# OpenTx-SPort-Bridge_v040.net
KiCad netlist of a schematic drawn in EAGLE
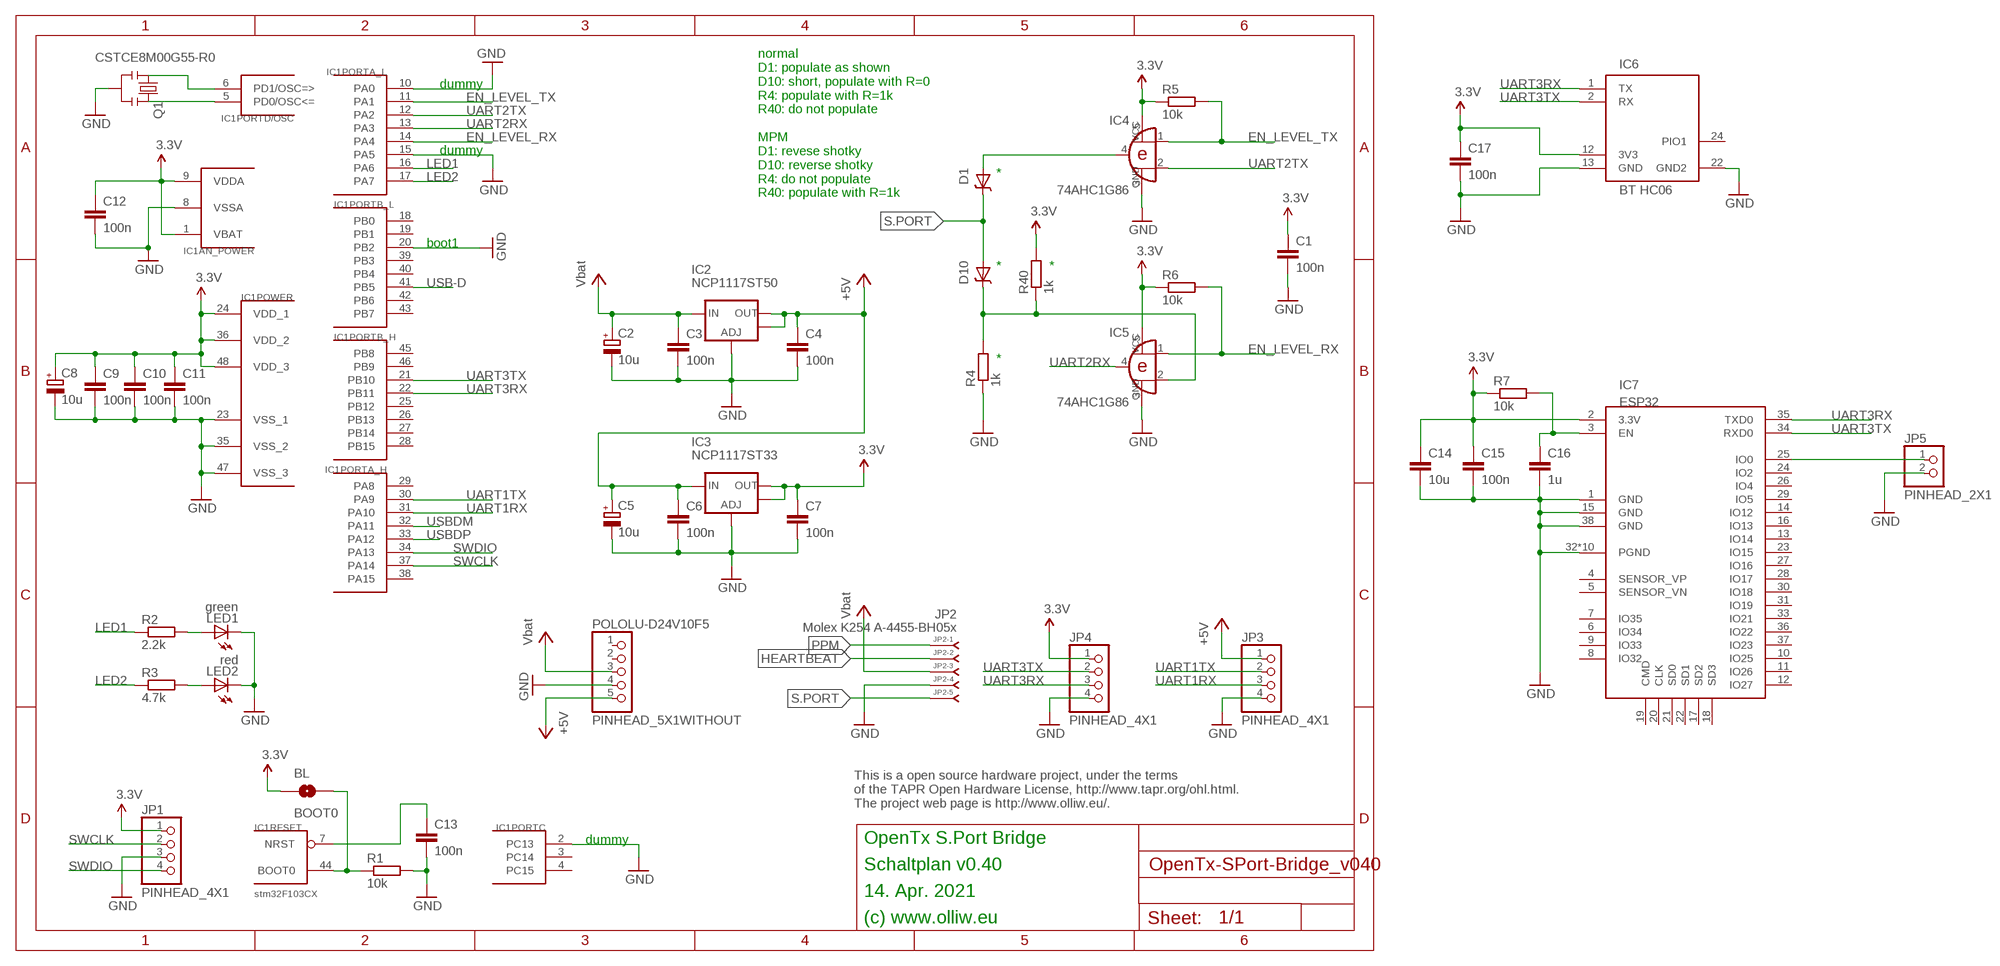
[diagram p0: schematic, sheet 1]

(export (version "E")
  (design (tool "Eeschema 10.0.6"))
  (components
    (comp (ref "BL")
      (value "BOOT0")
      (footprint "eagle-import:SJ_2S-NO")
      (libsource (lib "eagle-import") (part "SOLDERJUMPERNO"))
    )
    (comp (ref "C1")
      (value "100n")
      (footprint "eagle-import:C0603")
      (libsource (lib "eagle-import") (part "C-EUC0603"))
    )
    (comp (ref "C2")
      (value "10u")
      (footprint "eagle-import:SMC_A")
      (libsource (lib "eagle-import") (part "CPOL-EUSMCA"))
    )
    (comp (ref "C3")
      (value "100n")
      (footprint "eagle-import:C0603")
      (libsource (lib "eagle-import") (part "C-EUC0603"))
    )
    (comp (ref "C4")
      (value "100n")
      (footprint "eagle-import:C0603")
      (libsource (lib "eagle-import") (part "C-EUC0603"))
    )
    (comp (ref "C5")
      (value "10u")
      (footprint "eagle-import:SMC_A")
      (libsource (lib "eagle-import") (part "CPOL-EUSMCA"))
    )
    (comp (ref "C6")
      (value "100n")
      (footprint "eagle-import:C0603")
      (libsource (lib "eagle-import") (part "C-EUC0603"))
    )
    (comp (ref "C7")
      (value "100n")
      (footprint "eagle-import:C0603")
      (libsource (lib "eagle-import") (part "C-EUC0603"))
    )
    (comp (ref "C8")
      (value "10u")
      (footprint "eagle-import:SMC_A")
      (libsource (lib "eagle-import") (part "CPOL-EUSMCA"))
    )
    (comp (ref "C9")
      (value "100n")
      (footprint "eagle-import:C0603")
      (libsource (lib "eagle-import") (part "C-EUC0603"))
    )
    (comp (ref "C10")
      (value "100n")
      (footprint "eagle-import:C0603")
      (libsource (lib "eagle-import") (part "C-EUC0603"))
    )
    (comp (ref "C11")
      (value "100n")
      (footprint "eagle-import:C0603")
      (libsource (lib "eagle-import") (part "C-EUC0603"))
    )
    (comp (ref "C12")
      (value "100n")
      (footprint "eagle-import:C0603")
      (libsource (lib "eagle-import") (part "C-EUC0603"))
    )
    (comp (ref "C13")
      (value "100n")
      (footprint "eagle-import:C0603")
      (libsource (lib "eagle-import") (part "C-EUC0603"))
    )
    (comp (ref "C14")
      (value "10u")
      (footprint "eagle-import:C0805")
      (libsource (lib "eagle-import") (part "C-EUC0805"))
    )
    (comp (ref "C15")
      (value "100n")
      (footprint "eagle-import:C0603")
      (libsource (lib "eagle-import") (part "C-EUC0603"))
    )
    (comp (ref "C16")
      (value "1u")
      (footprint "eagle-import:C0603")
      (libsource (lib "eagle-import") (part "C-EUC0603"))
    )
    (comp (ref "C17")
      (value "100n")
      (footprint "eagle-import:C0603")
      (libsource (lib "eagle-import") (part "C-EUC0603"))
    )
    (comp (ref "D1")
      (value "PMEG3010ER")
      (footprint "eagle-import:SOD123W-DIODE")
      (libsource (lib "eagle-import") (part "DIODE-SCHOTTKYSOD123-W"))
    )
    (comp (ref "D10")
      (value "PMEG3010ER")
      (footprint "eagle-import:SOD123W-DIODE")
      (libsource (lib "eagle-import") (part "DIODE-SCHOTTKYSOD123-W"))
    )
    (comp (ref "IC1")
      (value "stm32F103CX")
      (footprint "eagle-import:TQFP48")
      (libsource (lib "eagle-import") (part "STM32F10XCXT6"))
    )
    (comp (ref "IC2")
      (value "NCP1117ST50")
      (footprint "eagle-import:SOT223")
      (libsource (lib "eagle-import") (part "V_REG_LM1117SOT223"))
    )
    (comp (ref "IC3")
      (value "NCP1117ST33")
      (footprint "eagle-import:SOT223")
      (libsource (lib "eagle-import") (part "V_REG_LM1117SOT223"))
    )
    (comp (ref "IC4")
      (value "74AHC1G86")
      (footprint "eagle-import:SOT23-5-VER1")
      (libsource (lib "eagle-import") (part "74AHC1G86"))
    )
    (comp (ref "IC5")
      (value "74AHC1G86")
      (footprint "eagle-import:SOT23-5-VER1")
      (libsource (lib "eagle-import") (part "74AHC1G86"))
    )
    (comp (ref "IC6")
      (value "BT HC06")
      (footprint "eagle-import:BT_HC05_BASIC")
      (libsource (lib "eagle-import") (part "HC06-BASIC"))
    )
    (comp (ref "IC7")
      (value "ESP32")
      (footprint "eagle-import:ESP-WROOM-32D")
      (libsource (lib "eagle-import") (part "ESP32"))
    )
    (comp (ref "JP1")
      (value "PINHEAD_4X1")
      (footprint "eagle-import:PINHEAD_4X1")
      (libsource (lib "eagle-import") (part "PINHEAD_4X1"))
    )
    (comp (ref "JP2")
      (value "Molex K254 A-4455-BH05x")
      (footprint "eagle-import:4455-B05")
      (libsource (lib "eagle-import") (part "4455-B05_S"))
    )
    (comp (ref "JP3")
      (value "PINHEAD_4X1")
      (footprint "eagle-import:PINHEAD_4X1")
      (libsource (lib "eagle-import") (part "PINHEAD_4X1"))
    )
    (comp (ref "JP4")
      (value "PINHEAD_4X1")
      (footprint "eagle-import:PINHEAD_4X1")
      (libsource (lib "eagle-import") (part "PINHEAD_4X1"))
    )
    (comp (ref "JP5")
      (value "PINHEAD_2X1")
      (footprint "eagle-import:PINHEAD_2X1")
      (libsource (lib "eagle-import") (part "PINHEAD_2X1"))
    )
    (comp (ref "LED1")
      (value "green")
      (footprint "eagle-import:LED3MM")
      (libsource (lib "eagle-import") (part "LED3MM"))
    )
    (comp (ref "LED2")
      (value "red")
      (footprint "eagle-import:LED3MM")
      (libsource (lib "eagle-import") (part "LED3MM"))
    )
    (comp (ref "POLOLU-D24V10F5")
      (value "PINHEAD_5X1WITHOUT")
      (footprint "eagle-import:PINHEAD_5X1_WO")
      (libsource (lib "eagle-import") (part "PINHEAD_5X1WITHOUT"))
    )
    (comp (ref "Q1")
      (value "CSTCE8M00G55-R0")
      (footprint "eagle-import:RESONATOR-SMD")
      (libsource (lib "eagle-import") (part "RESONATORSMD"))
    )
    (comp (ref "R1")
      (value "10k")
      (footprint "eagle-import:R0603")
      (libsource (lib "eagle-import") (part "R-EU_R0603"))
    )
    (comp (ref "R2")
      (value "2.2k")
      (footprint "eagle-import:R0603")
      (libsource (lib "eagle-import") (part "R-EU_R0603"))
    )
    (comp (ref "R3")
      (value "4.7k")
      (footprint "eagle-import:R0603")
      (libsource (lib "eagle-import") (part "R-EU_R0603"))
    )
    (comp (ref "R4")
      (value "1k")
      (footprint "eagle-import:R0603")
      (libsource (lib "eagle-import") (part "R-EU_R0603"))
    )
    (comp (ref "R5")
      (value "10k")
      (footprint "eagle-import:R0603")
      (libsource (lib "eagle-import") (part "R-EU_R0603"))
    )
    (comp (ref "R6")
      (value "10k")
      (footprint "eagle-import:R0603")
      (libsource (lib "eagle-import") (part "R-EU_R0603"))
    )
    (comp (ref "R7")
      (value "10k")
      (footprint "eagle-import:R0603")
      (libsource (lib "eagle-import") (part "R-EU_R0603"))
    )
    (comp (ref "R40")
      (value "1k")
      (footprint "eagle-import:R0603")
      (libsource (lib "eagle-import") (part "R-EU_R0603"))
    )
  )
  (nets
    (net (code "1") (name "+5V") (class "Default")
      (node (ref "C4") (pin "1") (pinfunction "1_1") (pintype "passive"))
      (node (ref "C5") (pin "+") (pinfunction "+_+") (pintype "passive"))
      (node (ref "C6") (pin "1") (pinfunction "1_1") (pintype "passive"))
      (node (ref "IC2") (pin "2") (pinfunction "OUT_2") (pintype "output"))
      (node (ref "IC2") (pin "4") (pinfunction "OUT_4") (pintype "output"))
      (node (ref "IC3") (pin "3") (pinfunction "IN_3") (pintype "input"))
      (node (ref "JP3") (pin "1") (pinfunction "1_1") (pintype "passive"))
      (node (ref "POLOLU-D24V10F5") (pin "5") (pinfunction "5_5") (pintype "passive"))
    )
    (net (code "2") (name "/EN_LEVEL_RX") (class "Default")
      (node (ref "IC1") (pin "14") (pinfunction "PA4_14") (pintype "bidirectional"))
      (node (ref "IC5") (pin "1") (pinfunction "I0_1") (pintype "input"))
      (node (ref "R6") (pin "2") (pinfunction "2_2") (pintype "passive"))
    )
    (net (code "3") (name "/EN_LEVEL_TX") (class "Default")
      (node (ref "IC1") (pin "11") (pinfunction "PA1_11") (pintype "bidirectional"))
      (node (ref "IC4") (pin "1") (pinfunction "I0_1") (pintype "input"))
      (node (ref "R5") (pin "2") (pinfunction "2_2") (pintype "passive"))
    )
    (net (code "4") (name "/LED1") (class "Default")
      (node (ref "IC1") (pin "16") (pinfunction "PA6_16") (pintype "bidirectional"))
      (node (ref "R2") (pin "1") (pinfunction "1_1") (pintype "passive"))
    )
    (net (code "5") (name "/LED2") (class "Default")
      (node (ref "IC1") (pin "17") (pinfunction "PA7_17") (pintype "bidirectional"))
      (node (ref "R3") (pin "1") (pinfunction "1_1") (pintype "passive"))
    )
    (net (code "6") (name "/SWCLK") (class "Default")
      (node (ref "IC1") (pin "37") (pinfunction "PA14_37") (pintype "bidirectional"))
      (node (ref "JP1") (pin "2") (pinfunction "2_2") (pintype "passive"))
    )
    (net (code "7") (name "/SWDIO") (class "Default")
      (node (ref "IC1") (pin "34") (pinfunction "PA13_34") (pintype "bidirectional"))
      (node (ref "JP1") (pin "4") (pinfunction "4_4") (pintype "passive"))
    )
    (net (code "8") (name "/UART1RX") (class "Default")
      (node (ref "IC1") (pin "31") (pinfunction "PA10_31") (pintype "bidirectional"))
      (node (ref "JP3") (pin "3") (pinfunction "3_3") (pintype "passive"))
    )
    (net (code "9") (name "/UART1TX") (class "Default")
      (node (ref "IC1") (pin "30") (pinfunction "PA9_30") (pintype "bidirectional"))
      (node (ref "JP3") (pin "2") (pinfunction "2_2") (pintype "passive"))
    )
    (net (code "10") (name "/UART2RX") (class "Default")
      (node (ref "IC1") (pin "13") (pinfunction "PA3_13") (pintype "bidirectional"))
      (node (ref "IC5") (pin "4") (pinfunction "O_4") (pintype "output"))
    )
    (net (code "11") (name "/UART2TX") (class "Default")
      (node (ref "IC1") (pin "12") (pinfunction "PA2_12") (pintype "bidirectional"))
      (node (ref "IC4") (pin "2") (pinfunction "I1_2") (pintype "input"))
    )
    (net (code "12") (name "/UART3RX") (class "Default")
      (node (ref "IC1") (pin "22") (pinfunction "PB11_22") (pintype "bidirectional"))
      (node (ref "IC6") (pin "1") (pinfunction "TX_1") (pintype "bidirectional"))
      (node (ref "IC7") (pin "35") (pinfunction "TXD0_35") (pintype "bidirectional"))
      (node (ref "JP4") (pin "3") (pinfunction "3_3") (pintype "passive"))
    )
    (net (code "13") (name "/UART3TX") (class "Default")
      (node (ref "IC1") (pin "21") (pinfunction "PB10_21") (pintype "bidirectional"))
      (node (ref "IC6") (pin "2") (pinfunction "RX_2") (pintype "bidirectional"))
      (node (ref "IC7") (pin "34") (pinfunction "RXD0_34") (pintype "bidirectional"))
      (node (ref "JP4") (pin "2") (pinfunction "2_2") (pintype "passive"))
    )
    (net (code "14") (name "/USB-D") (class "Default")
      (node (ref "IC1") (pin "41") (pinfunction "PB5_41") (pintype "bidirectional"))
    )
    (net (code "15") (name "/USBDM") (class "Default")
      (node (ref "IC1") (pin "32") (pinfunction "PA11_32") (pintype "bidirectional"))
    )
    (net (code "16") (name "/USBDP") (class "Default")
      (node (ref "IC1") (pin "33") (pinfunction "PA12_33") (pintype "bidirectional"))
    )
    (net (code "17") (name "3.3V") (class "Default")
      (node (ref "BL") (pin "1") (pinfunction "1_1") (pintype "passive"))
      (node (ref "C1") (pin "1") (pinfunction "1_1") (pintype "passive"))
      (node (ref "C10") (pin "1") (pinfunction "1_1") (pintype "passive"))
      (node (ref "C11") (pin "1") (pinfunction "1_1") (pintype "passive"))
      (node (ref "C12") (pin "1") (pinfunction "1_1") (pintype "passive"))
      (node (ref "C14") (pin "1") (pinfunction "1_1") (pintype "passive"))
      (node (ref "C15") (pin "1") (pinfunction "1_1") (pintype "passive"))
      (node (ref "C17") (pin "1") (pinfunction "1_1") (pintype "passive"))
      (node (ref "C7") (pin "1") (pinfunction "1_1") (pintype "passive"))
      (node (ref "C8") (pin "+") (pinfunction "+_+") (pintype "passive"))
      (node (ref "C9") (pin "1") (pinfunction "1_1") (pintype "passive"))
      (node (ref "IC1") (pin "1") (pinfunction "VBAT_1") (pintype "power_in"))
      (node (ref "IC1") (pin "24") (pinfunction "VDD_1_24") (pintype "power_in"))
      (node (ref "IC1") (pin "36") (pinfunction "VDD_2_36") (pintype "power_in"))
      (node (ref "IC1") (pin "48") (pinfunction "VDD_3_48") (pintype "power_in"))
      (node (ref "IC1") (pin "9") (pinfunction "VDDA_9") (pintype "power_in"))
      (node (ref "IC3") (pin "2") (pinfunction "OUT_2") (pintype "output"))
      (node (ref "IC3") (pin "4") (pinfunction "OUT_4") (pintype "output"))
      (node (ref "IC4") (pin "5") (pinfunction "VCC_5") (pintype "power_in"))
      (node (ref "IC5") (pin "5") (pinfunction "VCC_5") (pintype "power_in"))
      (node (ref "IC6") (pin "12") (pinfunction "3V3_12") (pintype "bidirectional"))
      (node (ref "IC7") (pin "2") (pinfunction "3.3V_2") (pintype "power_in"))
      (node (ref "JP1") (pin "1") (pinfunction "1_1") (pintype "passive"))
      (node (ref "JP4") (pin "1") (pinfunction "1_1") (pintype "passive"))
      (node (ref "R40") (pin "2") (pinfunction "2_2") (pintype "passive"))
      (node (ref "R5") (pin "1") (pinfunction "1_1") (pintype "passive"))
      (node (ref "R6") (pin "1") (pinfunction "1_1") (pintype "passive"))
      (node (ref "R7") (pin "1") (pinfunction "1_1") (pintype "passive"))
    )
    (net (code "18") (name "GND") (class "Default")
      (node (ref "C1") (pin "2") (pinfunction "2_2") (pintype "passive"))
      (node (ref "C10") (pin "2") (pinfunction "2_2") (pintype "passive"))
      (node (ref "C11") (pin "2") (pinfunction "2_2") (pintype "passive"))
      (node (ref "C12") (pin "2") (pinfunction "2_2") (pintype "passive"))
      (node (ref "C13") (pin "2") (pinfunction "2_2") (pintype "passive"))
      (node (ref "C14") (pin "2") (pinfunction "2_2") (pintype "passive"))
      (node (ref "C15") (pin "2") (pinfunction "2_2") (pintype "passive"))
      (node (ref "C16") (pin "2") (pinfunction "2_2") (pintype "passive"))
      (node (ref "C17") (pin "2") (pinfunction "2_2") (pintype "passive"))
      (node (ref "C2") (pin "-") (pinfunction "-_-") (pintype "passive"))
      (node (ref "C3") (pin "2") (pinfunction "2_2") (pintype "passive"))
      (node (ref "C4") (pin "2") (pinfunction "2_2") (pintype "passive"))
      (node (ref "C5") (pin "-") (pinfunction "-_-") (pintype "passive"))
      (node (ref "C6") (pin "2") (pinfunction "2_2") (pintype "passive"))
      (node (ref "C7") (pin "2") (pinfunction "2_2") (pintype "passive"))
      (node (ref "C8") (pin "-") (pinfunction "-_-") (pintype "passive"))
      (node (ref "C9") (pin "2") (pinfunction "2_2") (pintype "passive"))
      (node (ref "IC1") (pin "10") (pinfunction "PA0_10") (pintype "bidirectional"))
      (node (ref "IC1") (pin "15") (pinfunction "PA5_15") (pintype "bidirectional"))
      (node (ref "IC1") (pin "2") (pinfunction "PC13_2") (pintype "bidirectional"))
      (node (ref "IC1") (pin "20") (pinfunction "PB2_20") (pintype "bidirectional"))
      (node (ref "IC1") (pin "23") (pinfunction "VSS_1_23") (pintype "power_in"))
      (node (ref "IC1") (pin "35") (pinfunction "VSS_2_35") (pintype "power_in"))
      (node (ref "IC1") (pin "47") (pinfunction "VSS_3_47") (pintype "power_in"))
      (node (ref "IC1") (pin "8") (pinfunction "VSSA_8") (pintype "power_in"))
      (node (ref "IC2") (pin "1") (pinfunction "ADJ_1") (pintype "input"))
      (node (ref "IC3") (pin "1") (pinfunction "ADJ_1") (pintype "input"))
      (node (ref "IC4") (pin "3") (pinfunction "GND_3") (pintype "power_in"))
      (node (ref "IC5") (pin "3") (pinfunction "GND_3") (pintype "power_in"))
      (node (ref "IC6") (pin "13") (pinfunction "GND_13") (pintype "bidirectional"))
      (node (ref "IC6") (pin "22") (pinfunction "GND2_22") (pintype "bidirectional"))
      (node (ref "IC7") (pin "1") (pinfunction "GND_1") (pintype "power_in"))
      (node (ref "IC7") (pin "15") (pinfunction "GND_15") (pintype "power_in"))
      (node (ref "IC7") (pin "32") (pinfunction "PGND_32") (pintype "power_in"))
      (node (ref "IC7") (pin "38") (pinfunction "GND_38") (pintype "power_in"))
      (node (ref "IC7") (pin "39") (pinfunction "PGND_39") (pintype "power_in"))
      (node (ref "IC7") (pin "40") (pinfunction "PGND_40") (pintype "power_in"))
      (node (ref "IC7") (pin "41") (pinfunction "PGND_41") (pintype "power_in"))
      (node (ref "IC7") (pin "42") (pinfunction "PGND_42") (pintype "power_in"))
      (node (ref "IC7") (pin "43") (pinfunction "PGND_43") (pintype "power_in"))
      (node (ref "IC7") (pin "44") (pinfunction "PGND_44") (pintype "power_in"))
      (node (ref "IC7") (pin "45") (pinfunction "PGND_45") (pintype "power_in"))
      (node (ref "IC7") (pin "46") (pinfunction "PGND_46") (pintype "power_in"))
      (node (ref "IC7") (pin "47") (pinfunction "PGND_47") (pintype "power_in"))
      (node (ref "JP1") (pin "3") (pinfunction "3_3") (pintype "passive"))
      (node (ref "JP2") (pin "4") (pinfunction "J_4") (pintype "passive"))
      (node (ref "JP3") (pin "4") (pinfunction "4_4") (pintype "passive"))
      (node (ref "JP4") (pin "4") (pinfunction "4_4") (pintype "passive"))
      (node (ref "JP5") (pin "2") (pinfunction "2_2") (pintype "passive"))
      (node (ref "LED1") (pin "K") (pinfunction "C_K") (pintype "passive"))
      (node (ref "LED2") (pin "K") (pinfunction "C_K") (pintype "passive"))
      (node (ref "POLOLU-D24V10F5") (pin "4") (pinfunction "4_4") (pintype "passive"))
      (node (ref "Q1") (pin "2") (pinfunction "2_2") (pintype "passive"))
      (node (ref "R1") (pin "2") (pinfunction "2_2") (pintype "passive"))
      (node (ref "R4") (pin "1") (pinfunction "1_1") (pintype "passive"))
    )
    (net (code "19") (name "HEARTBEAT") (class "Default")
      (node (ref "JP2") (pin "2") (pinfunction "J_2") (pintype "passive"))
    )
    (net (code "20") (name "Net-(IC1G-PD0{slash}OSC<=)") (class "Default")
      (node (ref "IC1") (pin "5") (pinfunction "PD0/OSC<=_5") (pintype "bidirectional"))
      (node (ref "Q1") (pin "3") (pinfunction "3_3") (pintype "passive"))
    )
    (net (code "21") (name "Net-(IC1G-PD1{slash}OSC=>)") (class "Default")
      (node (ref "IC1") (pin "6") (pinfunction "PD1/OSC=>_6") (pintype "bidirectional"))
      (node (ref "Q1") (pin "1") (pinfunction "1_1") (pintype "passive"))
    )
    (net (code "22") (name "Net-(IC1I-BOOT0)") (class "Default")
      (node (ref "BL") (pin "2") (pinfunction "2_2") (pintype "passive"))
      (node (ref "IC1") (pin "44") (pinfunction "BOOT0_44") (pintype "input"))
      (node (ref "R1") (pin "1") (pinfunction "1_1") (pintype "passive"))
    )
    (net (code "23") (name "Net-(IC1I-NRST)") (class "Default")
      (node (ref "C13") (pin "1") (pinfunction "1_1") (pintype "passive"))
      (node (ref "IC1") (pin "7") (pinfunction "NRST_7") (pintype "input"))
    )
    (net (code "24") (name "Net-(IC4-O)") (class "Default")
      (node (ref "D1") (pin "A") (pinfunction "A_A") (pintype "passive"))
      (node (ref "IC4") (pin "4") (pinfunction "O_4") (pintype "output"))
    )
    (net (code "25") (name "Net-(IC5-I1)") (class "Default")
      (node (ref "D10") (pin "C") (pinfunction "C_C") (pintype "passive"))
      (node (ref "IC5") (pin "2") (pinfunction "I1_2") (pintype "input"))
      (node (ref "R4") (pin "2") (pinfunction "2_2") (pintype "passive"))
      (node (ref "R40") (pin "1") (pinfunction "1_1") (pintype "passive"))
    )
    (net (code "26") (name "Net-(IC7-EN)") (class "Default")
      (node (ref "C16") (pin "1") (pinfunction "1_1") (pintype "passive"))
      (node (ref "IC7") (pin "3") (pinfunction "EN_3") (pintype "input"))
      (node (ref "R7") (pin "2") (pinfunction "2_2") (pintype "passive"))
    )
    (net (code "27") (name "Net-(IC7-IO0)") (class "Default")
      (node (ref "IC7") (pin "25") (pinfunction "IO0_25") (pintype "bidirectional"))
      (node (ref "JP5") (pin "1") (pinfunction "1_1") (pintype "passive"))
    )
    (net (code "28") (name "Net-(LED1-PadA)") (class "Default")
      (node (ref "LED1") (pin "A") (pinfunction "A_A") (pintype "passive"))
      (node (ref "R2") (pin "2") (pinfunction "2_2") (pintype "passive"))
    )
    (net (code "29") (name "Net-(LED2-PadA)") (class "Default")
      (node (ref "LED2") (pin "A") (pinfunction "A_A") (pintype "passive"))
      (node (ref "R3") (pin "2") (pinfunction "2_2") (pintype "passive"))
    )
    (net (code "30") (name "PPM") (class "Default")
      (node (ref "JP2") (pin "1") (pinfunction "J_1") (pintype "passive"))
    )
    (net (code "31") (name "S.PORT") (class "Default")
      (node (ref "D1") (pin "C") (pinfunction "C_C") (pintype "passive"))
      (node (ref "D10") (pin "A") (pinfunction "A_A") (pintype "passive"))
      (node (ref "JP2") (pin "5") (pinfunction "J_5") (pintype "passive"))
    )
    (net (code "32") (name "Vbat") (class "Default")
      (node (ref "C2") (pin "+") (pinfunction "+_+") (pintype "passive"))
      (node (ref "C3") (pin "1") (pinfunction "1_1") (pintype "passive"))
      (node (ref "IC2") (pin "3") (pinfunction "IN_3") (pintype "input"))
      (node (ref "JP2") (pin "3") (pinfunction "J_3") (pintype "passive"))
      (node (ref "POLOLU-D24V10F5") (pin "3") (pinfunction "3_3") (pintype "passive"))
    )
    (net (code "33") (name "unconnected-(IC1B-PA8-Pad29)") (class "Default")
      (node (ref "IC1") (pin "29") (pinfunction "PA8_29") (pintype "bidirectional"))
    )
    (net (code "34") (name "unconnected-(IC1B-PA15-Pad38)") (class "Default")
      (node (ref "IC1") (pin "38") (pinfunction "PA15_38") (pintype "bidirectional"))
    )
    (net (code "35") (name "unconnected-(IC1D-PB8-Pad45)") (class "Default")
      (node (ref "IC1") (pin "45") (pinfunction "PB8_45") (pintype "bidirectional"))
    )
    (net (code "36") (name "unconnected-(IC1D-PB9-Pad46)") (class "Default")
      (node (ref "IC1") (pin "46") (pinfunction "PB9_46") (pintype "bidirectional"))
    )
    (net (code "37") (name "unconnected-(IC1D-PB12-Pad25)") (class "Default")
      (node (ref "IC1") (pin "25") (pinfunction "PB12_25") (pintype "bidirectional"))
    )
    (net (code "38") (name "unconnected-(IC1D-PB13-Pad26)") (class "Default")
      (node (ref "IC1") (pin "26") (pinfunction "PB13_26") (pintype "bidirectional"))
    )
    (net (code "39") (name "unconnected-(IC1D-PB14-Pad27)") (class "Default")
      (node (ref "IC1") (pin "27") (pinfunction "PB14_27") (pintype "bidirectional"))
    )
    (net (code "40") (name "unconnected-(IC1D-PB15-Pad28)") (class "Default")
      (node (ref "IC1") (pin "28") (pinfunction "PB15_28") (pintype "bidirectional"))
    )
    (net (code "41") (name "unconnected-(IC1E-PB0-Pad18)") (class "Default")
      (node (ref "IC1") (pin "18") (pinfunction "PB0_18") (pintype "bidirectional"))
    )
    (net (code "42") (name "unconnected-(IC1E-PB1-Pad19)") (class "Default")
      (node (ref "IC1") (pin "19") (pinfunction "PB1_19") (pintype "bidirectional"))
    )
    (net (code "43") (name "unconnected-(IC1E-PB3-Pad39)") (class "Default")
      (node (ref "IC1") (pin "39") (pinfunction "PB3_39") (pintype "bidirectional"))
    )
    (net (code "44") (name "unconnected-(IC1E-PB4-Pad40)") (class "Default")
      (node (ref "IC1") (pin "40") (pinfunction "PB4_40") (pintype "bidirectional"))
    )
    (net (code "45") (name "unconnected-(IC1E-PB6-Pad42)") (class "Default")
      (node (ref "IC1") (pin "42") (pinfunction "PB6_42") (pintype "bidirectional"))
    )
    (net (code "46") (name "unconnected-(IC1E-PB7-Pad43)") (class "Default")
      (node (ref "IC1") (pin "43") (pinfunction "PB7_43") (pintype "bidirectional"))
    )
    (net (code "47") (name "unconnected-(IC1F-PC14-Pad3)") (class "Default")
      (node (ref "IC1") (pin "3") (pinfunction "PC14_3") (pintype "bidirectional"))
    )
    (net (code "48") (name "unconnected-(IC1F-PC15-Pad4)") (class "Default")
      (node (ref "IC1") (pin "4") (pinfunction "PC15_4") (pintype "bidirectional"))
    )
    (net (code "49") (name "unconnected-(IC6-PIO1-Pad24)") (class "Default")
      (node (ref "IC6") (pin "24") (pinfunction "PIO1_24") (pintype "bidirectional"))
    )
    (net (code "50") (name "unconnected-(IC7-CLK-Pad20)") (class "Default")
      (node (ref "IC7") (pin "20") (pinfunction "CLK_20") (pintype "bidirectional"))
    )
    (net (code "51") (name "unconnected-(IC7-CMD-Pad19)") (class "Default")
      (node (ref "IC7") (pin "19") (pinfunction "CMD_19") (pintype "bidirectional"))
    )
    (net (code "52") (name "unconnected-(IC7-IO2-Pad24)") (class "Default")
      (node (ref "IC7") (pin "24") (pinfunction "IO2_24") (pintype "bidirectional"))
    )
    (net (code "53") (name "unconnected-(IC7-IO4-Pad26)") (class "Default")
      (node (ref "IC7") (pin "26") (pinfunction "IO4_26") (pintype "bidirectional"))
    )
    (net (code "54") (name "unconnected-(IC7-IO5-Pad29)") (class "Default")
      (node (ref "IC7") (pin "29") (pinfunction "IO5_29") (pintype "bidirectional"))
    )
    (net (code "55") (name "unconnected-(IC7-IO12-Pad14)") (class "Default")
      (node (ref "IC7") (pin "14") (pinfunction "IO12_14") (pintype "bidirectional"))
    )
    (net (code "56") (name "unconnected-(IC7-IO13-Pad16)") (class "Default")
      (node (ref "IC7") (pin "16") (pinfunction "IO13_16") (pintype "bidirectional"))
    )
    (net (code "57") (name "unconnected-(IC7-IO14-Pad13)") (class "Default")
      (node (ref "IC7") (pin "13") (pinfunction "IO14_13") (pintype "bidirectional"))
    )
    (net (code "58") (name "unconnected-(IC7-IO15-Pad23)") (class "Default")
      (node (ref "IC7") (pin "23") (pinfunction "IO15_23") (pintype "bidirectional"))
    )
    (net (code "59") (name "unconnected-(IC7-IO16-Pad27)") (class "Default")
      (node (ref "IC7") (pin "27") (pinfunction "IO16_27") (pintype "bidirectional"))
    )
    (net (code "60") (name "unconnected-(IC7-IO17-Pad28)") (class "Default")
      (node (ref "IC7") (pin "28") (pinfunction "IO17_28") (pintype "bidirectional"))
    )
    (net (code "61") (name "unconnected-(IC7-IO18-Pad30)") (class "Default")
      (node (ref "IC7") (pin "30") (pinfunction "IO18_30") (pintype "bidirectional"))
    )
    (net (code "62") (name "unconnected-(IC7-IO19-Pad31)") (class "Default")
      (node (ref "IC7") (pin "31") (pinfunction "IO19_31") (pintype "bidirectional"))
    )
    (net (code "63") (name "unconnected-(IC7-IO21-Pad33)") (class "Default")
      (node (ref "IC7") (pin "33") (pinfunction "IO21_33") (pintype "bidirectional"))
    )
    (net (code "64") (name "unconnected-(IC7-IO22-Pad36)") (class "Default")
      (node (ref "IC7") (pin "36") (pinfunction "IO22_36") (pintype "bidirectional"))
    )
    (net (code "65") (name "unconnected-(IC7-IO23-Pad37)") (class "Default")
      (node (ref "IC7") (pin "37") (pinfunction "IO23_37") (pintype "bidirectional"))
    )
    (net (code "66") (name "unconnected-(IC7-IO25-Pad10)") (class "Default")
      (node (ref "IC7") (pin "10") (pinfunction "IO25_10") (pintype "bidirectional"))
    )
    (net (code "67") (name "unconnected-(IC7-IO26-Pad11)") (class "Default")
      (node (ref "IC7") (pin "11") (pinfunction "IO26_11") (pintype "bidirectional"))
    )
    (net (code "68") (name "unconnected-(IC7-IO27-Pad12)") (class "Default")
      (node (ref "IC7") (pin "12") (pinfunction "IO27_12") (pintype "bidirectional"))
    )
    (net (code "69") (name "unconnected-(IC7-IO32-Pad8)") (class "Default")
      (node (ref "IC7") (pin "8") (pinfunction "IO32_8") (pintype "bidirectional"))
    )
    (net (code "70") (name "unconnected-(IC7-IO33-Pad9)") (class "Default")
      (node (ref "IC7") (pin "9") (pinfunction "IO33_9") (pintype "bidirectional"))
    )
    (net (code "71") (name "unconnected-(IC7-IO34-Pad6)") (class "Default")
      (node (ref "IC7") (pin "6") (pinfunction "IO34_6") (pintype "bidirectional"))
    )
    (net (code "72") (name "unconnected-(IC7-IO35-Pad7)") (class "Default")
      (node (ref "IC7") (pin "7") (pinfunction "IO35_7") (pintype "bidirectional"))
    )
    (net (code "73") (name "unconnected-(IC7-SD0-Pad21)") (class "Default")
      (node (ref "IC7") (pin "21") (pinfunction "SD0_21") (pintype "bidirectional"))
    )
    (net (code "74") (name "unconnected-(IC7-SD1-Pad22)") (class "Default")
      (node (ref "IC7") (pin "22") (pinfunction "SD1_22") (pintype "bidirectional"))
    )
    (net (code "75") (name "unconnected-(IC7-SD2-Pad17)") (class "Default")
      (node (ref "IC7") (pin "17") (pinfunction "SD2_17") (pintype "bidirectional"))
    )
    (net (code "76") (name "unconnected-(IC7-SD3-Pad18)") (class "Default")
      (node (ref "IC7") (pin "18") (pinfunction "SD3_18") (pintype "bidirectional"))
    )
    (net (code "77") (name "unconnected-(IC7-SENSOR_VN-Pad5)") (class "Default")
      (node (ref "IC7") (pin "5") (pinfunction "SENSOR_VN_5") (pintype "bidirectional"))
    )
    (net (code "78") (name "unconnected-(IC7-SENSOR_VP-Pad4)") (class "Default")
      (node (ref "IC7") (pin "4") (pinfunction "SENSOR_VP_4") (pintype "bidirectional"))
    )
    (net (code "79") (name "unconnected-(POLOLU-D24V10F5-Pad1)") (class "Default")
      (node (ref "POLOLU-D24V10F5") (pin "1") (pinfunction "1_1") (pintype "passive"))
    )
    (net (code "80") (name "unconnected-(POLOLU-D24V10F5-Pad2)") (class "Default")
      (node (ref "POLOLU-D24V10F5") (pin "2") (pinfunction "2_2") (pintype "passive"))
    )
  )
)
